# PART2.net
KiCad netlist of a schematic drawn in Altium Designer
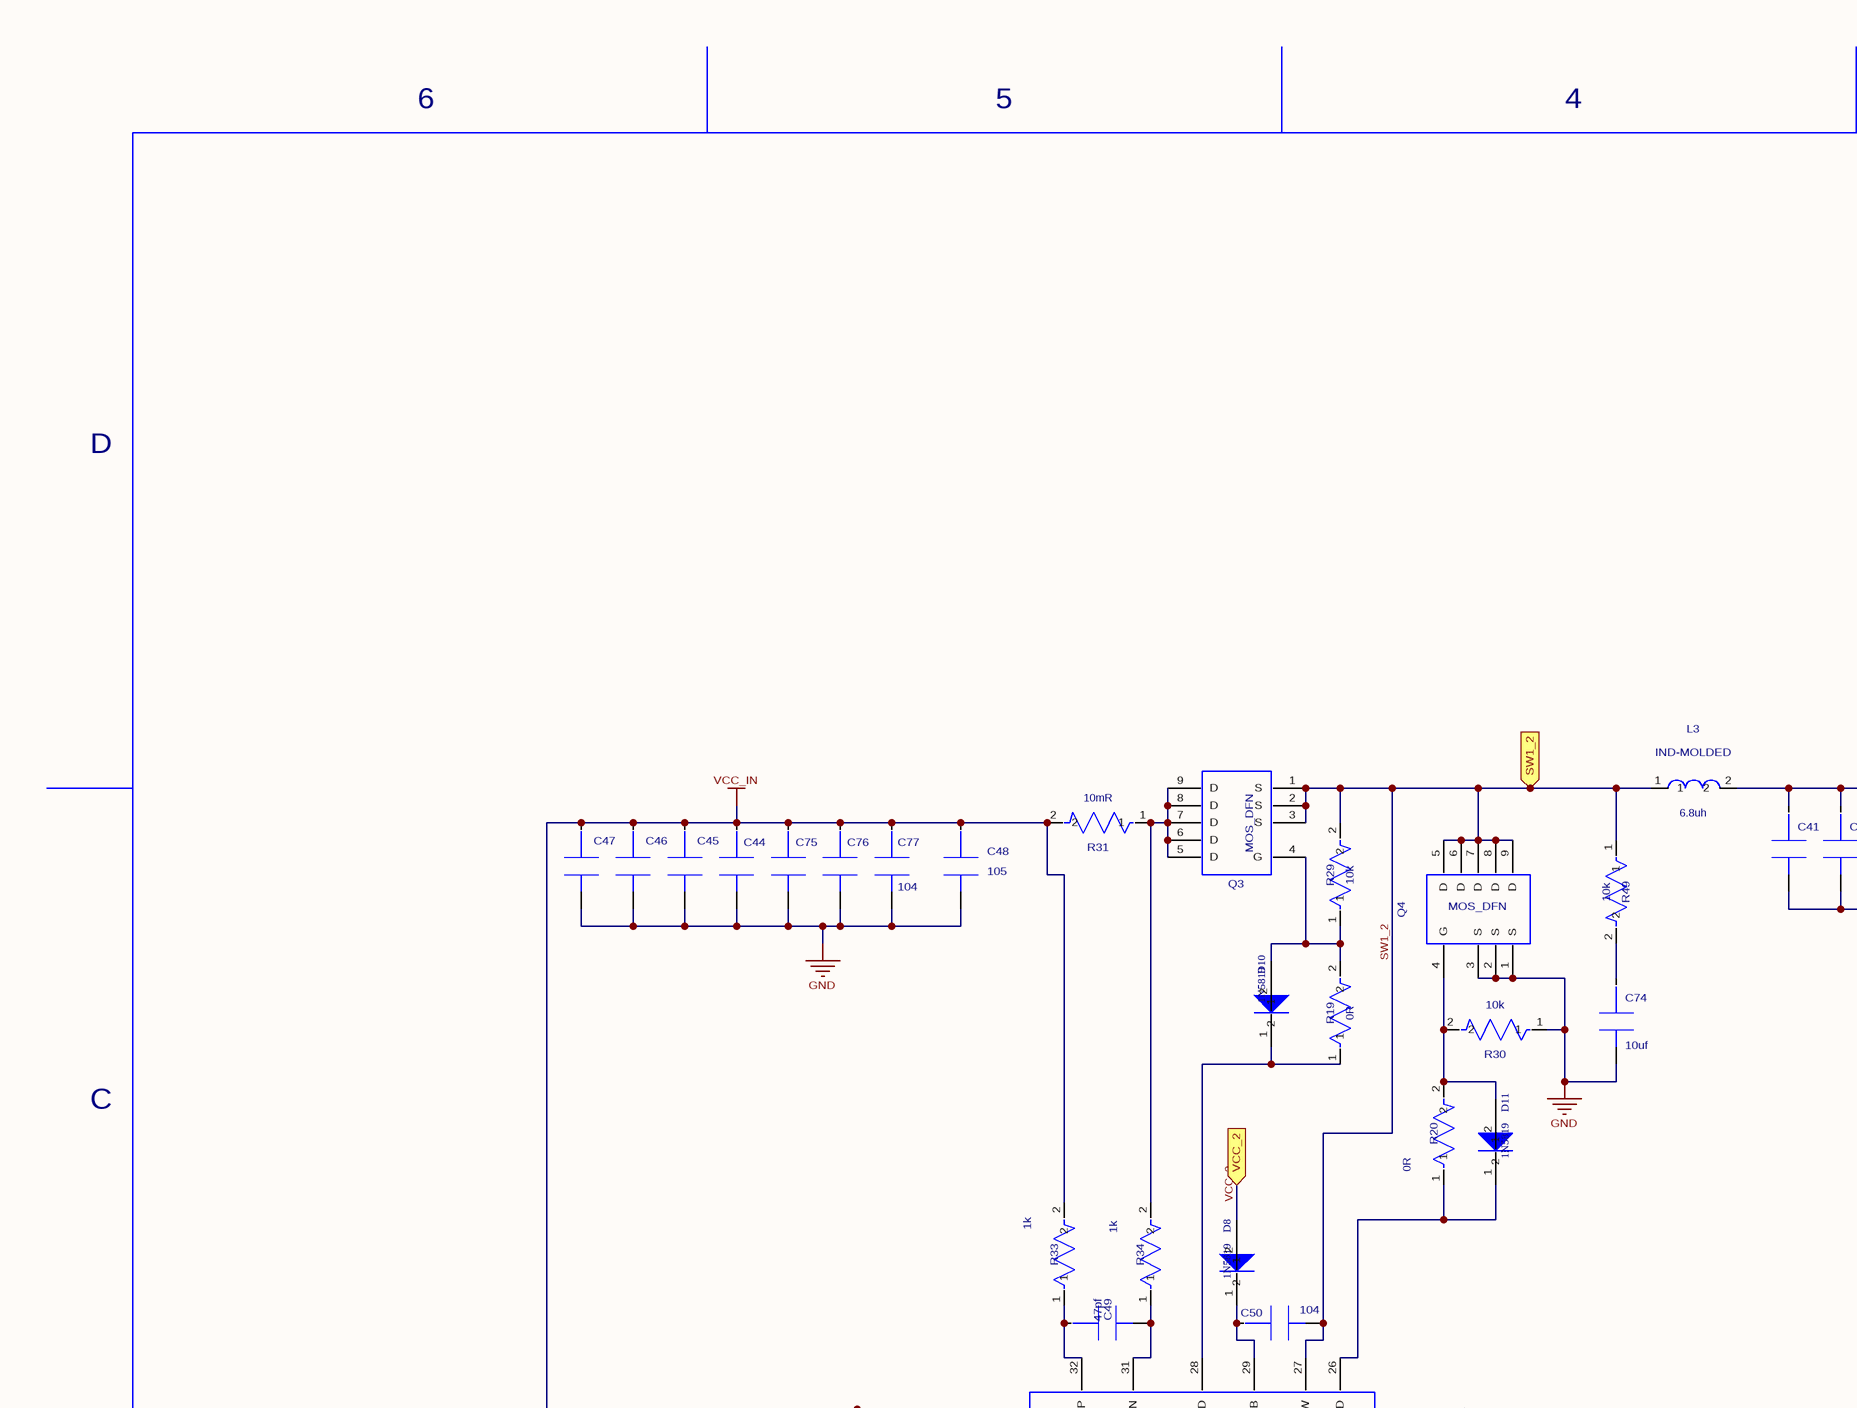
[diagram p0: PART2.SchDoc, top left]
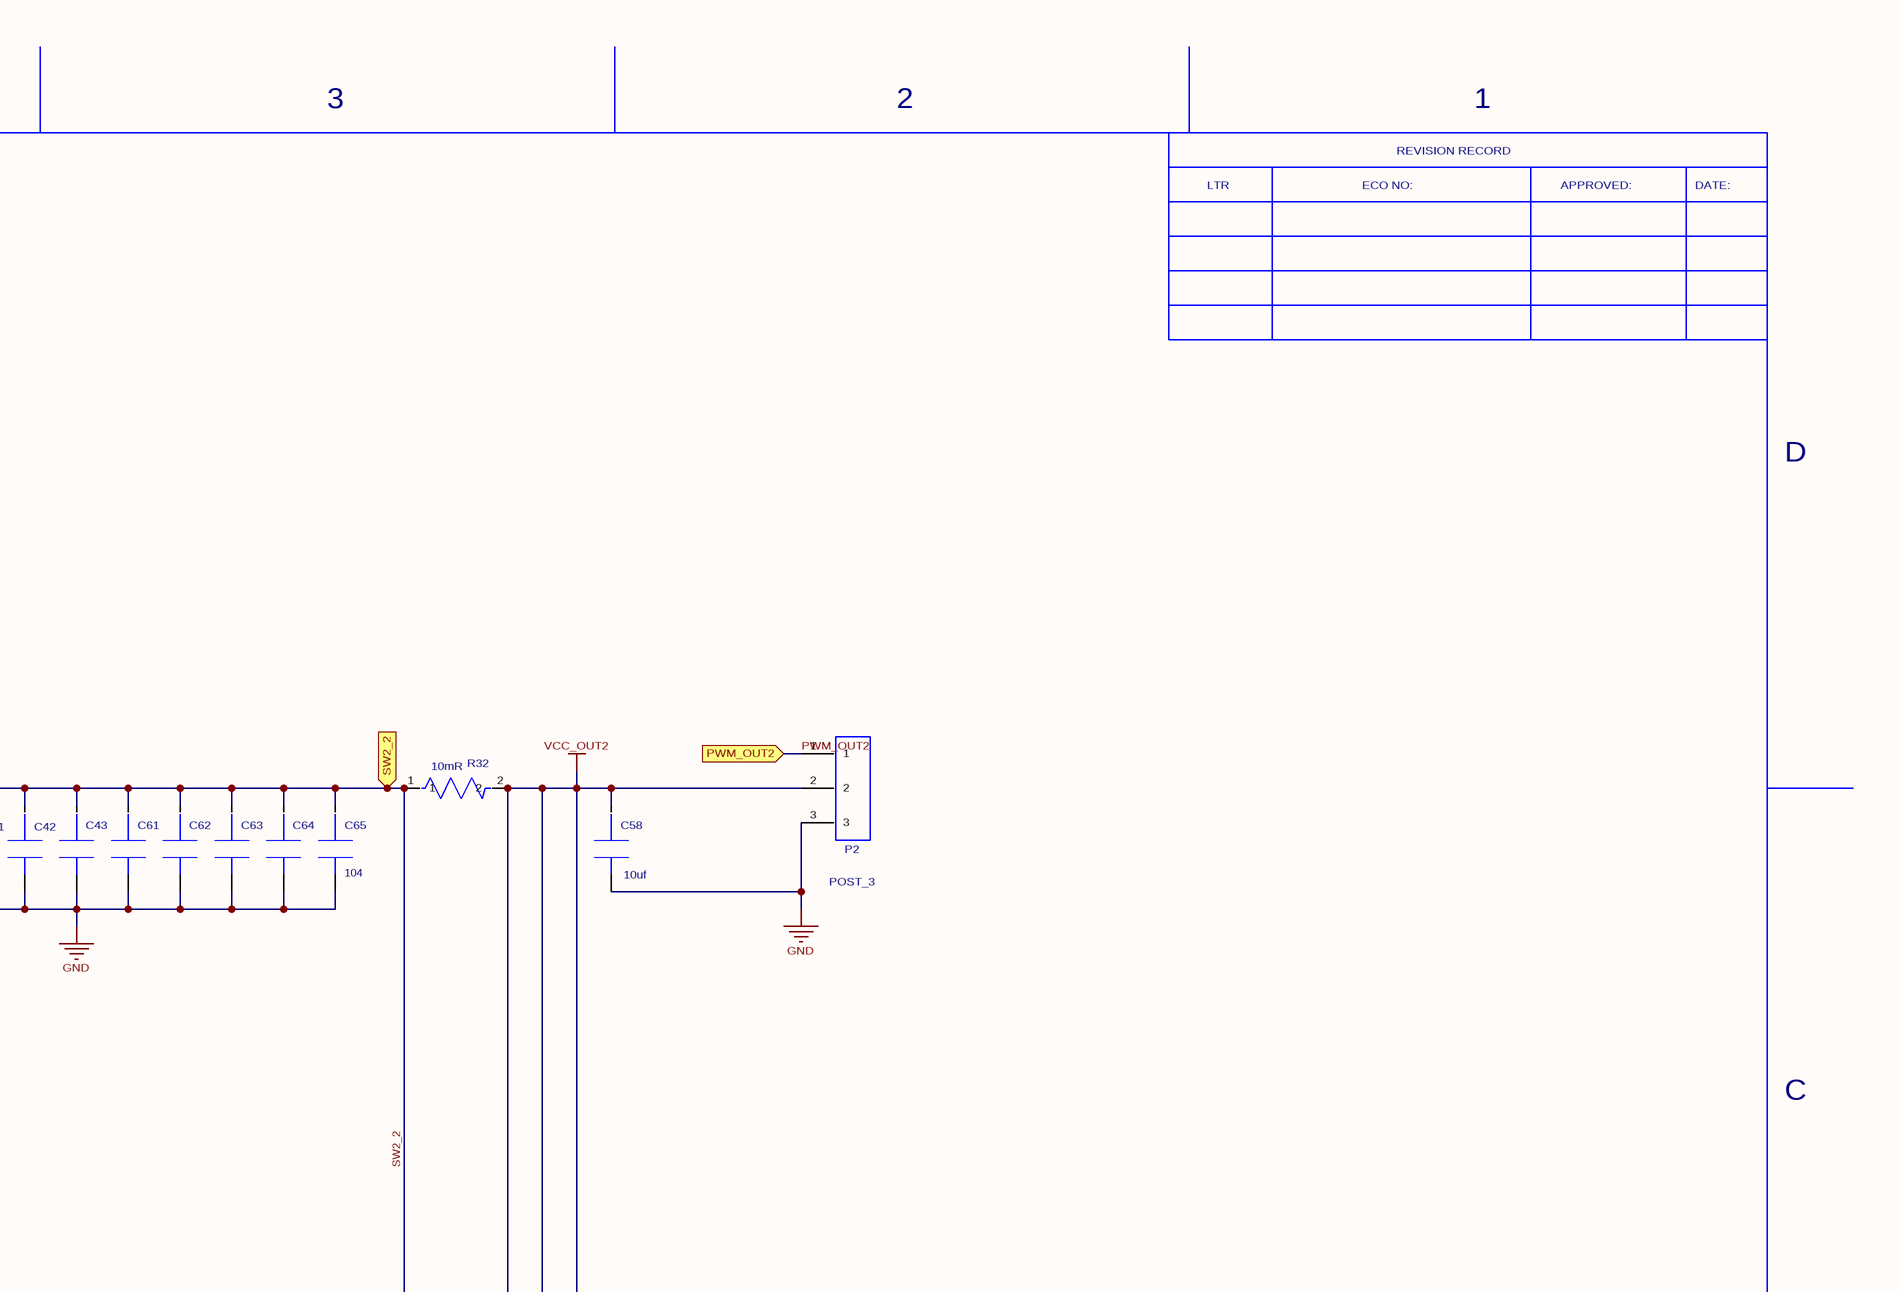
[diagram p1: PART2.SchDoc, top right]
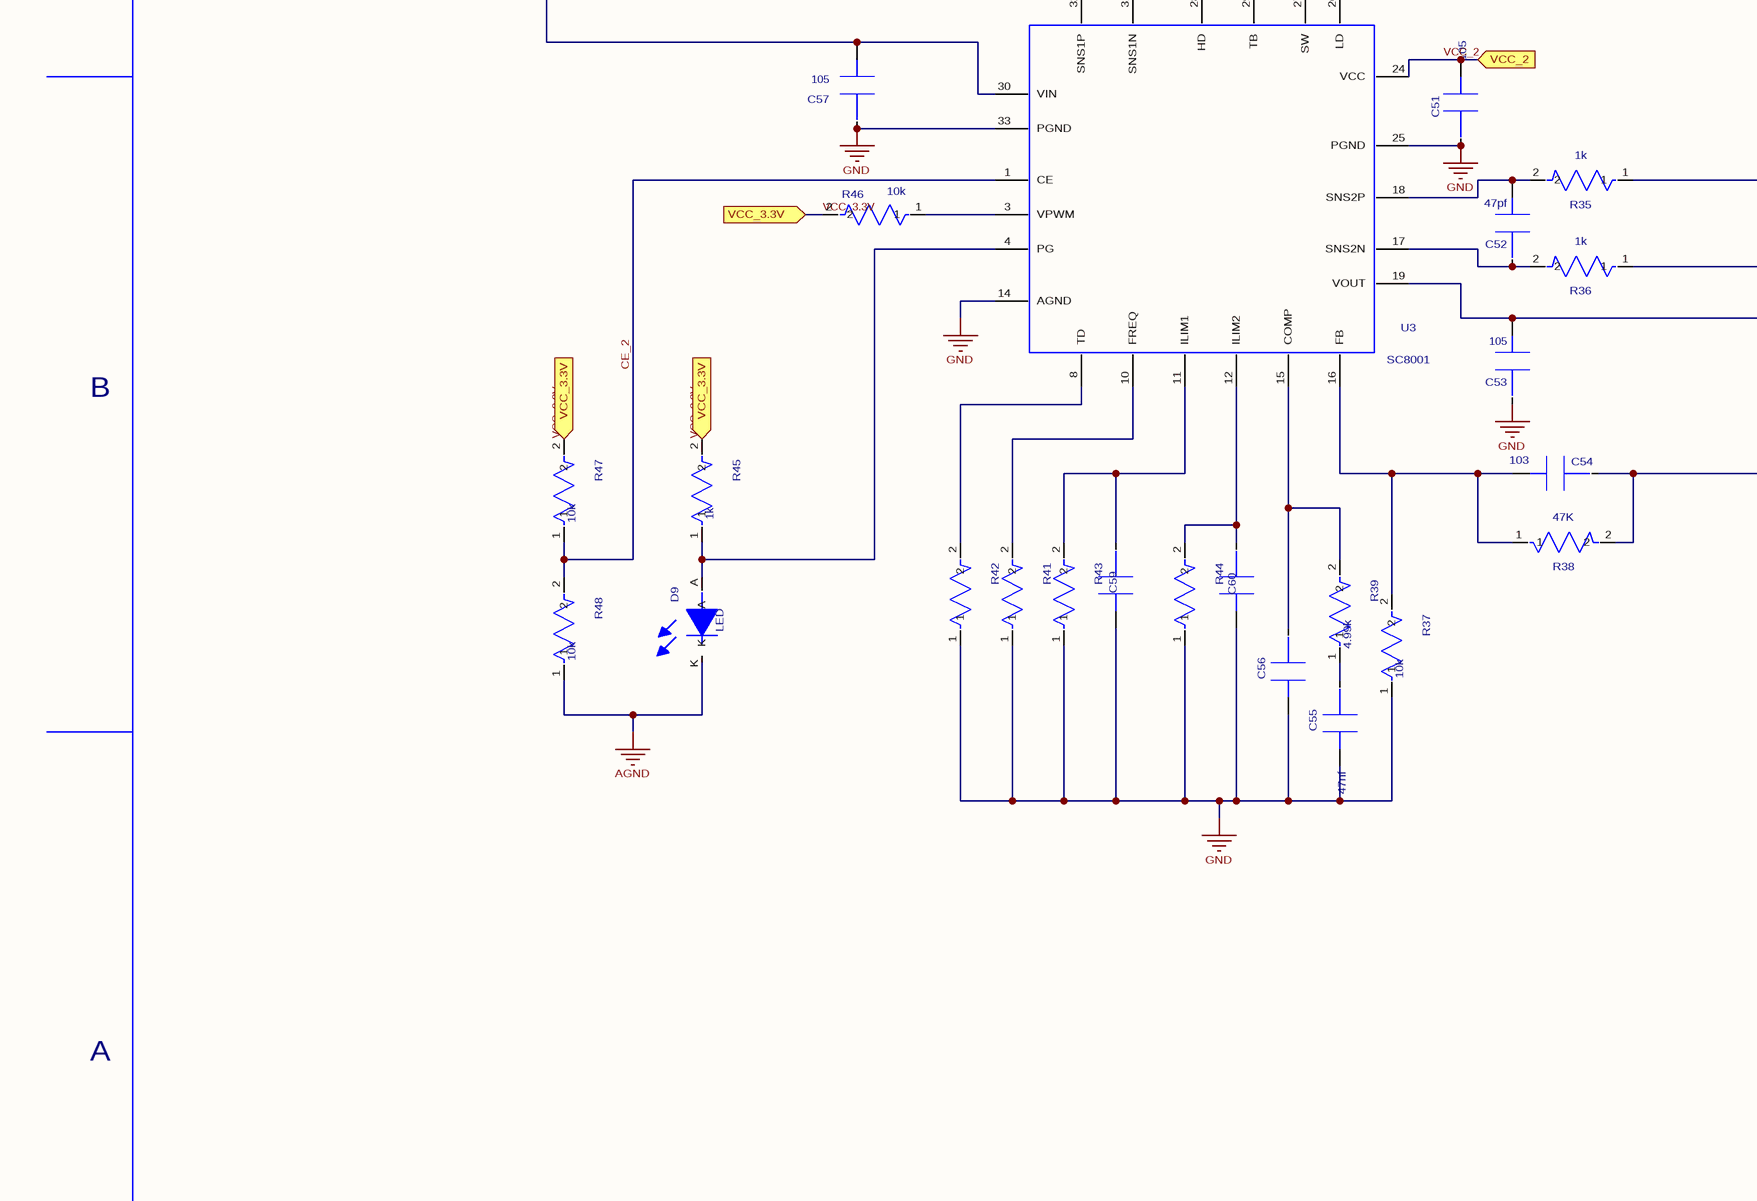
[diagram p2: PART2.SchDoc, bottom left]
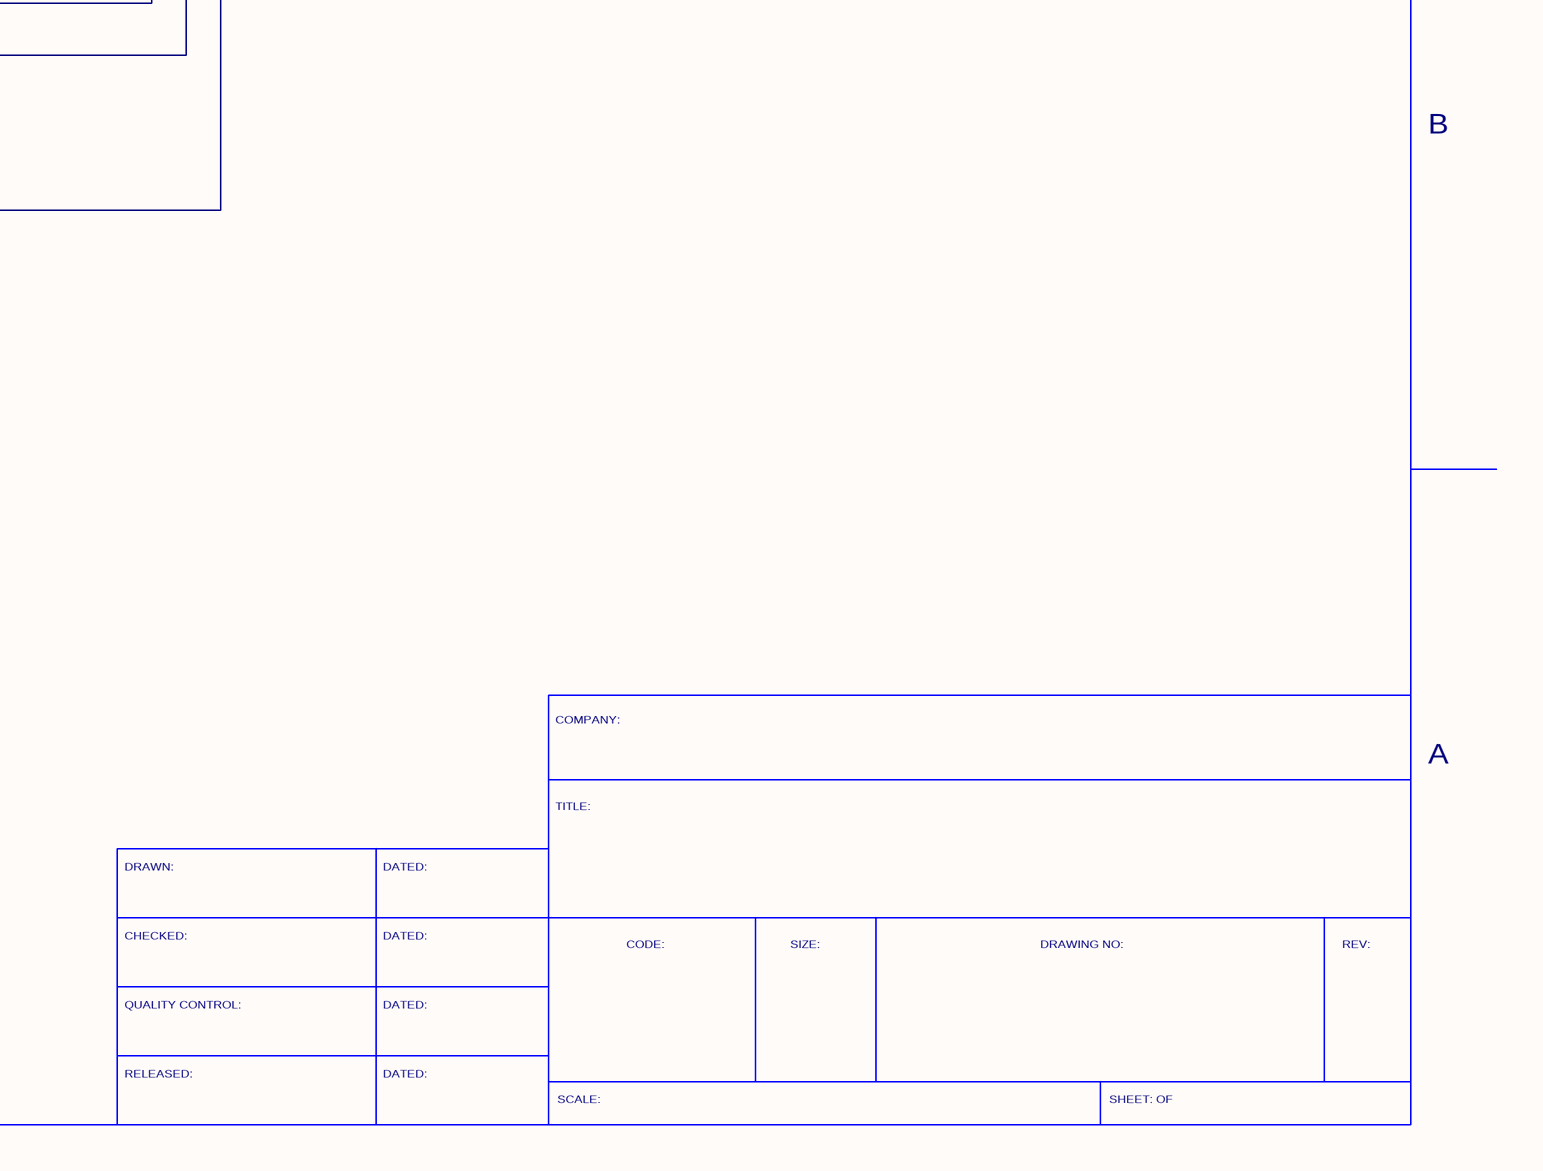
[diagram p3: PART2.SchDoc, bottom right]

(export (version "E")
  (design (tool "Eeschema 10.0.6"))
  (components
    (comp (ref "C41")
      (value "CAP-AE6.3")
      (footprint "CC6.56.5")
      (description "ALUMINUM ELECTROLYTIC CAP.")
      (libsource (lib "*") (part "CAP-AE6.3"))
    )
    (comp (ref "C42")
      (value "CAP-AE6.3")
      (footprint "CC6.56.5")
      (description "ALUMINUM ELECTROLYTIC CAP.")
      (libsource (lib "*") (part "CAP-AE6.3"))
    )
    (comp (ref "C43")
      (value "CAP-CFR04R-C")
      (footprint "1206C")
      (description "RADIAL FILM CAPACITOR, MIL-SPEC SIZE CFR04R SIZE 'C'")
      (fields (field (name "TOLERANCE") "???") (field (name "PART NUMBER") "TBD"))
      (libsource (lib "*") (part "CAP-CFR04R-C"))
    )
    (comp (ref "C44")
      (value "CAP-CFR04R-C")
      (footprint "1210C")
      (description "RADIAL FILM CAPACITOR, MIL-SPEC SIZE CFR04R SIZE 'C'")
      (fields (field (name "TOLERANCE") "???") (field (name "PART NUMBER") "TBD"))
      (libsource (lib "*") (part "CAP-CFR04R-C"))
    )
    (comp (ref "C45")
      (value "CAP-CFR04R-C")
      (footprint "1210C")
      (description "RADIAL FILM CAPACITOR, MIL-SPEC SIZE CFR04R SIZE 'C'")
      (fields (field (name "TOLERANCE") "???") (field (name "PART NUMBER") "TBD"))
      (libsource (lib "*") (part "CAP-CFR04R-C"))
    )
    (comp (ref "C46")
      (value "CAP-CFR04R-C")
      (footprint "1206C")
      (description "RADIAL FILM CAPACITOR, MIL-SPEC SIZE CFR04R SIZE 'C'")
      (fields (field (name "TOLERANCE") "???") (field (name "PART NUMBER") "TBD"))
      (libsource (lib "*") (part "CAP-CFR04R-C"))
    )
    (comp (ref "C47")
      (value "CAP-CFR04R-C")
      (footprint "1210C")
      (description "RADIAL FILM CAPACITOR, MIL-SPEC SIZE CFR04R SIZE 'C'")
      (fields (field (name "TOLERANCE") "???") (field (name "PART NUMBER") "TBD"))
      (libsource (lib "*") (part "CAP-CFR04R-C"))
    )
    (comp (ref "C48")
      (value "105")
      (footprint "0805C")
      (description "RADIAL FILM CAPACITOR, MIL-SPEC SIZE CFR04R SIZE 'C'")
      (fields (field (name "TOLERANCE") "???") (field (name "PART NUMBER") "TBD"))
      (libsource (lib "*") (part "CAP-CFR04R-C"))
    )
    (comp (ref "C49")
      (value "47pf")
      (footprint "0603C")
      (description "RADIAL FILM CAPACITOR, MIL-SPEC SIZE CFR04R SIZE 'C'")
      (fields (field (name "TOLERANCE") "???") (field (name "PART NUMBER") "TBD"))
      (libsource (lib "*") (part "CAP-CFR04R-C"))
    )
    (comp (ref "C50")
      (value "104")
      (footprint "0805C")
      (description "RADIAL FILM CAPACITOR, MIL-SPEC SIZE CFR04R SIZE 'C'")
      (fields (field (name "TOLERANCE") "???") (field (name "PART NUMBER") "TBD"))
      (libsource (lib "*") (part "CAP-CFR04R-C"))
    )
    (comp (ref "C51")
      (value "105")
      (footprint "0805C")
      (description "RADIAL FILM CAPACITOR, MIL-SPEC SIZE CFR04R SIZE 'C'")
      (fields (field (name "TOLERANCE") "???") (field (name "PART NUMBER") "TBD"))
      (libsource (lib "*") (part "CAP-CFR04R-C"))
    )
    (comp (ref "C52")
      (value "47pf")
      (footprint "0603C")
      (description "RADIAL FILM CAPACITOR, MIL-SPEC SIZE CFR04R SIZE 'C'")
      (fields (field (name "TOLERANCE") "???") (field (name "PART NUMBER") "TBD"))
      (libsource (lib "*") (part "CAP-CFR04R-C"))
    )
    (comp (ref "C53")
      (value "105")
      (footprint "0805C")
      (description "RADIAL FILM CAPACITOR, MIL-SPEC SIZE CFR04R SIZE 'C'")
      (fields (field (name "TOLERANCE") "???") (field (name "PART NUMBER") "TBD"))
      (libsource (lib "*") (part "CAP-CFR04R-C"))
    )
    (comp (ref "C54")
      (value "103")
      (footprint "0603C")
      (description "RADIAL FILM CAPACITOR, MIL-SPEC SIZE CFR04R SIZE 'C'")
      (fields (field (name "TOLERANCE") "???") (field (name "PART NUMBER") "TBD"))
      (libsource (lib "*") (part "CAP-CFR04R-C"))
    )
    (comp (ref "C55")
      (value "47nf")
      (footprint "0603C")
      (description "RADIAL FILM CAPACITOR, MIL-SPEC SIZE CFR04R SIZE 'C'")
      (fields (field (name "TOLERANCE") "???") (field (name "PART NUMBER") "TBD"))
      (libsource (lib "*") (part "CAP-CFR04R-C"))
    )
    (comp (ref "C56")
      (value "CAP-CFR04R-C")
      (footprint "0603C")
      (description "RADIAL FILM CAPACITOR, MIL-SPEC SIZE CFR04R SIZE 'C'")
      (fields (field (name "TOLERANCE") "???") (field (name "PART NUMBER") "TBD"))
      (libsource (lib "*") (part "CAP-CFR04R-C"))
    )
    (comp (ref "C57")
      (value "105")
      (footprint "0805C")
      (description "RADIAL FILM CAPACITOR, MIL-SPEC SIZE CFR04R SIZE 'C'")
      (fields (field (name "TOLERANCE") "???") (field (name "PART NUMBER") "TBD"))
      (libsource (lib "*") (part "CAP-CFR04R-C"))
    )
    (comp (ref "C58")
      (value "10uf")
      (footprint "1206C")
      (description "RADIAL FILM CAPACITOR, MIL-SPEC SIZE CFR04R SIZE 'C'")
      (fields (field (name "TOLERANCE") "???") (field (name "PART NUMBER") "TBD"))
      (libsource (lib "*") (part "CAP-CFR04R-C"))
    )
    (comp (ref "C59")
      (value "CAP-CFR04R-C")
      (footprint "0603C")
      (description "RADIAL FILM CAPACITOR, MIL-SPEC SIZE CFR04R SIZE 'C'")
      (fields (field (name "TOLERANCE") "???") (field (name "PART NUMBER") "TBD"))
      (libsource (lib "*") (part "CAP-CFR04R-C"))
    )
    (comp (ref "C60")
      (value "CAP-CFR04R-C")
      (footprint "0603C")
      (description "RADIAL FILM CAPACITOR, MIL-SPEC SIZE CFR04R SIZE 'C'")
      (fields (field (name "TOLERANCE") "???") (field (name "PART NUMBER") "TBD"))
      (libsource (lib "*") (part "CAP-CFR04R-C"))
    )
    (comp (ref "C61")
      (value "CAP-CFR04R-C")
      (footprint "1206C")
      (description "RADIAL FILM CAPACITOR, MIL-SPEC SIZE CFR04R SIZE 'C'")
      (fields (field (name "TOLERANCE") "???") (field (name "PART NUMBER") "TBD"))
      (libsource (lib "*") (part "CAP-CFR04R-C"))
    )
    (comp (ref "C62")
      (value "CAP-CFR04R-C")
      (footprint "1206C")
      (description "RADIAL FILM CAPACITOR, MIL-SPEC SIZE CFR04R SIZE 'C'")
      (fields (field (name "TOLERANCE") "???") (field (name "PART NUMBER") "TBD"))
      (libsource (lib "*") (part "CAP-CFR04R-C"))
    )
    (comp (ref "C63")
      (value "CAP-CFR04R-C")
      (footprint "1206C")
      (description "RADIAL FILM CAPACITOR, MIL-SPEC SIZE CFR04R SIZE 'C'")
      (fields (field (name "TOLERANCE") "???") (field (name "PART NUMBER") "TBD"))
      (libsource (lib "*") (part "CAP-CFR04R-C"))
    )
    (comp (ref "C64")
      (value "CAP-CFR04R-C")
      (footprint "1206C")
      (description "RADIAL FILM CAPACITOR, MIL-SPEC SIZE CFR04R SIZE 'C'")
      (fields (field (name "TOLERANCE") "???") (field (name "PART NUMBER") "TBD"))
      (libsource (lib "*") (part "CAP-CFR04R-C"))
    )
    (comp (ref "C65")
      (value "104")
      (footprint "1206C")
      (description "RADIAL FILM CAPACITOR, MIL-SPEC SIZE CFR04R SIZE 'C'")
      (fields (field (name "TOLERANCE") "???") (field (name "PART NUMBER") "TBD"))
      (libsource (lib "*") (part "CAP-CFR04R-C"))
    )
    (comp (ref "C74")
      (value "10uf")
      (footprint "0805C")
      (description "RADIAL FILM CAPACITOR, MIL-SPEC SIZE CFR04R SIZE 'C'")
      (fields (field (name "TOLERANCE") "???") (field (name "PART NUMBER") "TBD"))
      (libsource (lib "*") (part "CAP-CFR04R-C"))
    )
    (comp (ref "C75")
      (value "CAP-CFR04R-C")
      (footprint "1210C")
      (description "RADIAL FILM CAPACITOR, MIL-SPEC SIZE CFR04R SIZE 'C'")
      (fields (field (name "TOLERANCE") "???") (field (name "PART NUMBER") "TBD"))
      (libsource (lib "*") (part "CAP-CFR04R-C"))
    )
    (comp (ref "C76")
      (value "CAP-CFR04R-C")
      (footprint "1210C")
      (description "RADIAL FILM CAPACITOR, MIL-SPEC SIZE CFR04R SIZE 'C'")
      (fields (field (name "TOLERANCE") "???") (field (name "PART NUMBER") "TBD"))
      (libsource (lib "*") (part "CAP-CFR04R-C"))
    )
    (comp (ref "C77")
      (value "104")
      (footprint "0805C")
      (description "RADIAL FILM CAPACITOR, MIL-SPEC SIZE CFR04R SIZE 'C'")
      (fields (field (name "TOLERANCE") "???") (field (name "PART NUMBER") "TBD"))
      (libsource (lib "*") (part "CAP-CFR04R-C"))
    )
    (comp (ref "D8")
      (value "DIODE_1N4148")
      (footprint "SOD-123_L2.8-W1.8-LS3.7-RD")
      (description "High Conductance Fast Diode")
      (fields (field (name "PUBLISHER") "Altium Limited"))
      (libsource (lib "*") (part "DIODE_1N4148"))
    )
    (comp (ref "D9")
      (value "LED")
      (footprint "0805D")
      (description "LIGHT EMITTING DIODE")
      (libsource (lib "*") (part "LED"))
    )
    (comp (ref "D10")
      (value "DIODE_1N4148")
      (footprint "SOD-123_L2.8-W1.8-LS3.7-RD")
      (description "High Conductance Fast Diode")
      (fields (field (name "PUBLISHER") "Altium Limited"))
      (libsource (lib "*") (part "DIODE_1N4148"))
    )
    (comp (ref "D11")
      (value "DIODE_1N4148")
      (footprint "SOD-123_L2.8-W1.8-LS3.7-RD")
      (description "High Conductance Fast Diode")
      (fields (field (name "PUBLISHER") "Altium Limited"))
      (libsource (lib "*") (part "DIODE_1N4148"))
    )
    (comp (ref "L3")
      (value "IND-MOLDED")
      (footprint "1040L")
      (description "MOLDED INDUCTOR, 0.5\" PIN SPACING")
      (fields (field (name "ALTIUM_VALUE") "6.8uh"))
      (libsource (lib "*") (part "IND-MOLDED"))
    )
    (comp (ref "P2") (value "POST_3") (footprint "POST_3") (libsource (lib "*") (part "POST_3")))
    (comp (ref "Q3") (value "MOS_DFN") (footprint "DFN-8_5X6") (libsource (lib "*") (part "MOS_DFN")))
    (comp (ref "Q4") (value "MOS_DFN") (footprint "DFN-8_5X6") (libsource (lib "*") (part "MOS_DFN")))
    (comp (ref "R19")
      (value "0R")
      (footprint "0603R")
      (description "WIRE WOUND RESISTOR 3.4 X 7.05 MM")
      (fields (field (name "Comment") "RES-WR1"))
      (libsource (lib "*") (part "RES-WR1"))
    )
    (comp (ref "R20")
      (value "0R")
      (footprint "0603R")
      (description "WIRE WOUND RESISTOR 3.4 X 7.05 MM")
      (fields (field (name "Comment") "RES-WR1"))
      (libsource (lib "*") (part "RES-WR1"))
    )
    (comp (ref "R29")
      (value "10k")
      (footprint "0603R")
      (description "WIRE WOUND RESISTOR 3.4 X 7.05 MM")
      (fields (field (name "Comment") "RES-WR1"))
      (libsource (lib "*") (part "RES-WR1"))
    )
    (comp (ref "R30")
      (value "10k")
      (footprint "0603R")
      (description "WIRE WOUND RESISTOR 3.4 X 7.05 MM")
      (fields (field (name "Comment") "RES-WR1"))
      (libsource (lib "*") (part "RES-WR1"))
    )
    (comp (ref "R31")
      (value "10mR")
      (footprint "1206C")
      (description "WIRE WOUND RESISTOR 3.4 X 7.05 MM")
      (fields (field (name "Comment") "RES-WR1"))
      (libsource (lib "*") (part "RES-WR1"))
    )
    (comp (ref "R32")
      (value "10mR")
      (footprint "1206C")
      (description "WIRE WOUND RESISTOR 3.4 X 7.05 MM")
      (fields (field (name "Comment") "RES-WR1"))
      (libsource (lib "*") (part "RES-WR1"))
    )
    (comp (ref "R33")
      (value "1k")
      (footprint "0603R")
      (description "WIRE WOUND RESISTOR 3.4 X 7.05 MM")
      (fields (field (name "Comment") "RES-WR1"))
      (libsource (lib "*") (part "RES-WR1"))
    )
    (comp (ref "R34")
      (value "1k")
      (footprint "0603R")
      (description "WIRE WOUND RESISTOR 3.4 X 7.05 MM")
      (fields (field (name "Comment") "RES-WR1"))
      (libsource (lib "*") (part "RES-WR1"))
    )
    (comp (ref "R35")
      (value "1k")
      (footprint "0603R")
      (description "WIRE WOUND RESISTOR 3.4 X 7.05 MM")
      (fields (field (name "Comment") "RES-WR1"))
      (libsource (lib "*") (part "RES-WR1"))
    )
    (comp (ref "R36")
      (value "1k")
      (footprint "0603R")
      (description "WIRE WOUND RESISTOR 3.4 X 7.05 MM")
      (fields (field (name "Comment") "RES-WR1"))
      (libsource (lib "*") (part "RES-WR1"))
    )
    (comp (ref "R37")
      (value "10k")
      (footprint "0603R")
      (description "WIRE WOUND RESISTOR 3.4 X 7.05 MM")
      (fields (field (name "Comment") "RES-WR1"))
      (libsource (lib "*") (part "RES-WR1"))
    )
    (comp (ref "R38")
      (value "47K")
      (footprint "0603R")
      (description "WIRE WOUND RESISTOR 3.4 X 7.05 MM")
      (fields (field (name "Comment") "RES-WR1"))
      (libsource (lib "*") (part "RES-WR1"))
    )
    (comp (ref "R39")
      (value "4.99k")
      (footprint "0603R")
      (description "WIRE WOUND RESISTOR 3.4 X 7.05 MM")
      (fields (field (name "Comment") "RES-WR1"))
      (libsource (lib "*") (part "RES-WR1"))
    )
    (comp (ref "R41")
      (value "RES-WR1")
      (footprint "0603R")
      (description "WIRE WOUND RESISTOR 3.4 X 7.05 MM")
      (libsource (lib "*") (part "RES-WR1"))
    )
    (comp (ref "R42")
      (value "RES-WR1")
      (footprint "0603R")
      (description "WIRE WOUND RESISTOR 3.4 X 7.05 MM")
      (libsource (lib "*") (part "RES-WR1"))
    )
    (comp (ref "R43")
      (value "RES-WR1")
      (footprint "0603R")
      (description "WIRE WOUND RESISTOR 3.4 X 7.05 MM")
      (libsource (lib "*") (part "RES-WR1"))
    )
    (comp (ref "R44")
      (value "RES-WR1")
      (footprint "0603R")
      (description "WIRE WOUND RESISTOR 3.4 X 7.05 MM")
      (libsource (lib "*") (part "RES-WR1"))
    )
    (comp (ref "R45")
      (value "1k")
      (footprint "0805R")
      (description "WIRE WOUND RESISTOR 3.4 X 7.05 MM")
      (fields (field (name "Comment") "RES-WR1"))
      (libsource (lib "*") (part "RES-WR1"))
    )
    (comp (ref "R46")
      (value "10k")
      (footprint "0805R")
      (description "WIRE WOUND RESISTOR 3.4 X 7.05 MM")
      (fields (field (name "Comment") "RES-WR1"))
      (libsource (lib "*") (part "RES-WR1"))
    )
    (comp (ref "R47")
      (value "10k")
      (footprint "0805R")
      (description "WIRE WOUND RESISTOR 3.4 X 7.05 MM")
      (fields (field (name "Comment") "RES-WR1"))
      (libsource (lib "*") (part "RES-WR1"))
    )
    (comp (ref "R48")
      (value "10k")
      (footprint "0805R")
      (description "WIRE WOUND RESISTOR 3.4 X 7.05 MM")
      (fields (field (name "Comment") "RES-WR1"))
      (libsource (lib "*") (part "RES-WR1"))
    )
    (comp (ref "R49")
      (value "10k")
      (footprint "1206C")
      (description "WIRE WOUND RESISTOR 3.4 X 7.05 MM")
      (fields (field (name "Comment") "RES-WR1"))
      (libsource (lib "*") (part "RES-WR1"))
    )
    (comp (ref "U3")
      (value "SC8001")
      (footprint "QFN-32_L4.0-W4.0-P0.40-BL-EP2.7")
      (libsource (lib "*") (part "SC8001"))
    )
  )
  (nets
    (net (code "1") (name "/CE_2") (class "Default")
      (node (ref "R47") (pin "1") (pinfunction "1_1") (pintype "passive"))
      (node (ref "R48") (pin "2") (pinfunction "2_2") (pintype "passive"))
      (node (ref "U3") (pin "1") (pinfunction "CE_1") (pintype "passive"))
    )
    (net (code "2") (name "/PWM_OUT2") (class "Default")
      (node (ref "P2") (pin "1") (pinfunction "1_1") (pintype "passive"))
    )
    (net (code "3") (name "/SW1_2") (class "Default")
      (node (ref "C50") (pin "2") (pinfunction "2_2") (pintype "passive"))
      (node (ref "L3") (pin "1") (pinfunction "1_1") (pintype "passive"))
      (node (ref "Q3") (pin "1") (pinfunction "S_1") (pintype "passive"))
      (node (ref "Q3") (pin "2") (pinfunction "S_2") (pintype "passive"))
      (node (ref "Q3") (pin "3") (pinfunction "S_3") (pintype "passive"))
      (node (ref "Q4") (pin "5") (pinfunction "D_5") (pintype "passive"))
      (node (ref "Q4") (pin "6") (pinfunction "D_6") (pintype "passive"))
      (node (ref "Q4") (pin "7") (pinfunction "D_7") (pintype "passive"))
      (node (ref "Q4") (pin "8") (pinfunction "D_8") (pintype "passive"))
      (node (ref "Q4") (pin "9") (pinfunction "D_9") (pintype "passive"))
      (node (ref "R29") (pin "2") (pinfunction "2_2") (pintype "passive"))
      (node (ref "R49") (pin "1") (pinfunction "1_1") (pintype "passive"))
      (node (ref "U3") (pin "27") (pinfunction "SW_27") (pintype "passive"))
    )
    (net (code "4") (name "/SW2_2") (class "Default")
      (node (ref "C41") (pin "1") (pinfunction "1_1") (pintype "passive"))
      (node (ref "C42") (pin "1") (pinfunction "1_1") (pintype "passive"))
      (node (ref "C43") (pin "1") (pinfunction "1_1") (pintype "passive"))
      (node (ref "C61") (pin "1") (pinfunction "1_1") (pintype "passive"))
      (node (ref "C62") (pin "1") (pinfunction "1_1") (pintype "passive"))
      (node (ref "C63") (pin "1") (pinfunction "1_1") (pintype "passive"))
      (node (ref "C64") (pin "1") (pinfunction "1_1") (pintype "passive"))
      (node (ref "C65") (pin "1") (pinfunction "1_1") (pintype "passive"))
      (node (ref "L3") (pin "2") (pinfunction "2_2") (pintype "passive"))
      (node (ref "R32") (pin "1") (pinfunction "1_1") (pintype "passive"))
      (node (ref "R35") (pin "1") (pinfunction "1_1") (pintype "passive"))
    )
    (net (code "5") (name "/VCC_2") (class "Default")
      (node (ref "C51") (pin "2") (pinfunction "2_2") (pintype "passive"))
      (node (ref "D8") (pin "2") (pinfunction "2_2") (pintype "passive"))
      (node (ref "U3") (pin "24") (pinfunction "VCC_24") (pintype "passive"))
    )
    (net (code "6") (name "/VCC_3.3V") (class "Default")
      (node (ref "R45") (pin "2") (pinfunction "2_2") (pintype "passive"))
      (node (ref "R46") (pin "2") (pinfunction "2_2") (pintype "passive"))
      (node (ref "R47") (pin "2") (pinfunction "2_2") (pintype "passive"))
    )
    (net (code "7") (name "AGND") (class "Default")
      (node (ref "D9") (pin "K") (pinfunction "K_K") (pintype "passive"))
      (node (ref "R48") (pin "1") (pinfunction "1_1") (pintype "passive"))
    )
    (net (code "8") (name "GND") (class "Default")
      (node (ref "C41") (pin "2") (pinfunction "2_2") (pintype "passive"))
      (node (ref "C42") (pin "2") (pinfunction "2_2") (pintype "passive"))
      (node (ref "C43") (pin "2") (pinfunction "2_2") (pintype "passive"))
      (node (ref "C44") (pin "2") (pinfunction "2_2") (pintype "passive"))
      (node (ref "C45") (pin "2") (pinfunction "2_2") (pintype "passive"))
      (node (ref "C46") (pin "2") (pinfunction "2_2") (pintype "passive"))
      (node (ref "C47") (pin "2") (pinfunction "2_2") (pintype "passive"))
      (node (ref "C48") (pin "2") (pinfunction "2_2") (pintype "passive"))
      (node (ref "C51") (pin "1") (pinfunction "1_1") (pintype "passive"))
      (node (ref "C53") (pin "1") (pinfunction "1_1") (pintype "passive"))
      (node (ref "C55") (pin "2") (pinfunction "2_2") (pintype "passive"))
      (node (ref "C56") (pin "2") (pinfunction "2_2") (pintype "passive"))
      (node (ref "C57") (pin "1") (pinfunction "1_1") (pintype "passive"))
      (node (ref "C58") (pin "2") (pinfunction "2_2") (pintype "passive"))
      (node (ref "C59") (pin "2") (pinfunction "2_2") (pintype "passive"))
      (node (ref "C60") (pin "2") (pinfunction "2_2") (pintype "passive"))
      (node (ref "C61") (pin "2") (pinfunction "2_2") (pintype "passive"))
      (node (ref "C62") (pin "2") (pinfunction "2_2") (pintype "passive"))
      (node (ref "C63") (pin "2") (pinfunction "2_2") (pintype "passive"))
      (node (ref "C64") (pin "2") (pinfunction "2_2") (pintype "passive"))
      (node (ref "C65") (pin "2") (pinfunction "2_2") (pintype "passive"))
      (node (ref "C74") (pin "2") (pinfunction "2_2") (pintype "passive"))
      (node (ref "C75") (pin "2") (pinfunction "2_2") (pintype "passive"))
      (node (ref "C76") (pin "2") (pinfunction "2_2") (pintype "passive"))
      (node (ref "C77") (pin "2") (pinfunction "2_2") (pintype "passive"))
      (node (ref "P2") (pin "3") (pinfunction "3_3") (pintype "passive"))
      (node (ref "Q4") (pin "1") (pinfunction "S_1") (pintype "passive"))
      (node (ref "Q4") (pin "2") (pinfunction "S_2") (pintype "passive"))
      (node (ref "Q4") (pin "3") (pinfunction "S_3") (pintype "passive"))
      (node (ref "R30") (pin "1") (pinfunction "1_1") (pintype "passive"))
      (node (ref "R37") (pin "1") (pinfunction "1_1") (pintype "passive"))
      (node (ref "R41") (pin "1") (pinfunction "1_1") (pintype "passive"))
      (node (ref "R42") (pin "1") (pinfunction "1_1") (pintype "passive"))
      (node (ref "R43") (pin "1") (pinfunction "1_1") (pintype "passive"))
      (node (ref "R44") (pin "1") (pinfunction "1_1") (pintype "passive"))
      (node (ref "U3") (pin "14") (pinfunction "AGND_14") (pintype "passive"))
      (node (ref "U3") (pin "25") (pinfunction "PGND_25") (pintype "passive"))
      (node (ref "U3") (pin "33") (pinfunction "PGND_33") (pintype "passive"))
    )
    (net (code "9") (name "Net-(C55-Pad1)") (class "Default")
      (node (ref "C55") (pin "1") (pinfunction "1_1") (pintype "passive"))
      (node (ref "R39") (pin "1") (pinfunction "1_1") (pintype "passive"))
    )
    (net (code "10") (name "Net-(C74-Pad1)") (class "Default")
      (node (ref "C74") (pin "1") (pinfunction "1_1") (pintype "passive"))
      (node (ref "R49") (pin "2") (pinfunction "2_2") (pintype "passive"))
    )
    (net (code "11") (name "Net-(Q3-D-Pad5)") (class "Default")
      (node (ref "Q3") (pin "5") (pinfunction "D_5") (pintype "passive"))
      (node (ref "Q3") (pin "6") (pinfunction "D_6") (pintype "passive"))
      (node (ref "Q3") (pin "7") (pinfunction "D_7") (pintype "passive"))
      (node (ref "Q3") (pin "8") (pinfunction "D_8") (pintype "passive"))
      (node (ref "Q3") (pin "9") (pinfunction "D_9") (pintype "passive"))
      (node (ref "R31") (pin "1") (pinfunction "1_1") (pintype "passive"))
      (node (ref "R34") (pin "2") (pinfunction "2_2") (pintype "passive"))
    )
    (net (code "12") (name "Net-(Q3-G)") (class "Default")
      (node (ref "D10") (pin "2") (pinfunction "2_2") (pintype "passive"))
      (node (ref "Q3") (pin "4") (pinfunction "G_4") (pintype "passive"))
      (node (ref "R19") (pin "2") (pinfunction "2_2") (pintype "passive"))
      (node (ref "R29") (pin "1") (pinfunction "1_1") (pintype "passive"))
    )
    (net (code "13") (name "Net-(Q4-G)") (class "Default")
      (node (ref "D11") (pin "2") (pinfunction "2_2") (pintype "passive"))
      (node (ref "Q4") (pin "4") (pinfunction "G_4") (pintype "passive"))
      (node (ref "R20") (pin "2") (pinfunction "2_2") (pintype "passive"))
      (node (ref "R30") (pin "2") (pinfunction "2_2") (pintype "passive"))
    )
    (net (code "14") (name "Net-(U3-COMP)") (class "Default")
      (node (ref "C56") (pin "1") (pinfunction "1_1") (pintype "passive"))
      (node (ref "R39") (pin "2") (pinfunction "2_2") (pintype "passive"))
      (node (ref "U3") (pin "15") (pinfunction "COMP_15") (pintype "passive"))
    )
    (net (code "15") (name "Net-(U3-FB)") (class "Default")
      (node (ref "C54") (pin "2") (pinfunction "2_2") (pintype "passive"))
      (node (ref "R37") (pin "2") (pinfunction "2_2") (pintype "passive"))
      (node (ref "R38") (pin "1") (pinfunction "1_1") (pintype "passive"))
      (node (ref "U3") (pin "16") (pinfunction "FB_16") (pintype "passive"))
    )
    (net (code "16") (name "Net-(U3-FREQ)") (class "Default")
      (node (ref "R41") (pin "2") (pinfunction "2_2") (pintype "passive"))
      (node (ref "U3") (pin "10") (pinfunction "FREQ_10") (pintype "passive"))
    )
    (net (code "17") (name "Net-(U3-HD)") (class "Default")
      (node (ref "D10") (pin "1") (pinfunction "1_1") (pintype "passive"))
      (node (ref "R19") (pin "1") (pinfunction "1_1") (pintype "passive"))
      (node (ref "U3") (pin "28") (pinfunction "HD_28") (pintype "passive"))
    )
    (net (code "18") (name "Net-(U3-ILIM1)") (class "Default")
      (node (ref "C59") (pin "1") (pinfunction "1_1") (pintype "passive"))
      (node (ref "R43") (pin "2") (pinfunction "2_2") (pintype "passive"))
      (node (ref "U3") (pin "11") (pinfunction "ILIM1_11") (pintype "passive"))
    )
    (net (code "19") (name "Net-(U3-ILIM2)") (class "Default")
      (node (ref "C60") (pin "1") (pinfunction "1_1") (pintype "passive"))
      (node (ref "R44") (pin "2") (pinfunction "2_2") (pintype "passive"))
      (node (ref "U3") (pin "12") (pinfunction "ILIM2_12") (pintype "passive"))
    )
    (net (code "20") (name "Net-(U3-LD)") (class "Default")
      (node (ref "D11") (pin "1") (pinfunction "1_1") (pintype "passive"))
      (node (ref "R20") (pin "1") (pinfunction "1_1") (pintype "passive"))
      (node (ref "U3") (pin "26") (pinfunction "LD_26") (pintype "passive"))
    )
    (net (code "21") (name "Net-(U3-PG)") (class "Default")
      (node (ref "D9") (pin "A") (pinfunction "A_A") (pintype "passive"))
      (node (ref "R45") (pin "1") (pinfunction "1_1") (pintype "passive"))
      (node (ref "U3") (pin "4") (pinfunction "PG_4") (pintype "passive"))
    )
    (net (code "22") (name "Net-(U3-SNS1N)") (class "Default")
      (node (ref "C49") (pin "2") (pinfunction "2_2") (pintype "passive"))
      (node (ref "R34") (pin "1") (pinfunction "1_1") (pintype "passive"))
      (node (ref "U3") (pin "31") (pinfunction "SNS1N_31") (pintype "passive"))
    )
    (net (code "23") (name "Net-(U3-SNS1P)") (class "Default")
      (node (ref "C49") (pin "1") (pinfunction "1_1") (pintype "passive"))
      (node (ref "R33") (pin "1") (pinfunction "1_1") (pintype "passive"))
      (node (ref "U3") (pin "32") (pinfunction "SNS1P_32") (pintype "passive"))
    )
    (net (code "24") (name "Net-(U3-SNS2N)") (class "Default")
      (node (ref "C52") (pin "1") (pinfunction "1_1") (pintype "passive"))
      (node (ref "R36") (pin "2") (pinfunction "2_2") (pintype "passive"))
      (node (ref "U3") (pin "17") (pinfunction "SNS2N_17") (pintype "passive"))
    )
    (net (code "25") (name "Net-(U3-SNS2P)") (class "Default")
      (node (ref "C52") (pin "2") (pinfunction "2_2") (pintype "passive"))
      (node (ref "R35") (pin "2") (pinfunction "2_2") (pintype "passive"))
      (node (ref "U3") (pin "18") (pinfunction "SNS2P_18") (pintype "passive"))
    )
    (net (code "26") (name "Net-(U3-TB)") (class "Default")
      (node (ref "C50") (pin "1") (pinfunction "1_1") (pintype "passive"))
      (node (ref "D8") (pin "1") (pinfunction "1_1") (pintype "passive"))
      (node (ref "U3") (pin "29") (pinfunction "TB_29") (pintype "passive"))
    )
    (net (code "27") (name "Net-(U3-TD)") (class "Default")
      (node (ref "R42") (pin "2") (pinfunction "2_2") (pintype "passive"))
      (node (ref "U3") (pin "8") (pinfunction "TD_8") (pintype "passive"))
    )
    (net (code "28") (name "Net-(U3-VPWM)") (class "Default")
      (node (ref "R46") (pin "1") (pinfunction "1_1") (pintype "passive"))
      (node (ref "U3") (pin "3") (pinfunction "VPWM_3") (pintype "passive"))
    )
    (net (code "29") (name "VCC_IN") (class "Default")
      (node (ref "C44") (pin "1") (pinfunction "1_1") (pintype "passive"))
      (node (ref "C45") (pin "1") (pinfunction "1_1") (pintype "passive"))
      (node (ref "C46") (pin "1") (pinfunction "1_1") (pintype "passive"))
      (node (ref "C47") (pin "1") (pinfunction "1_1") (pintype "passive"))
      (node (ref "C48") (pin "1") (pinfunction "1_1") (pintype "passive"))
      (node (ref "C57") (pin "2") (pinfunction "2_2") (pintype "passive"))
      (node (ref "C75") (pin "1") (pinfunction "1_1") (pintype "passive"))
      (node (ref "C76") (pin "1") (pinfunction "1_1") (pintype "passive"))
      (node (ref "C77") (pin "1") (pinfunction "1_1") (pintype "passive"))
      (node (ref "R31") (pin "2") (pinfunction "2_2") (pintype "passive"))
      (node (ref "R33") (pin "2") (pinfunction "2_2") (pintype "passive"))
      (node (ref "U3") (pin "30") (pinfunction "VIN_30") (pintype "passive"))
    )
    (net (code "30") (name "VCC_OUT2") (class "Default")
      (node (ref "C53") (pin "2") (pinfunction "2_2") (pintype "passive"))
      (node (ref "C54") (pin "1") (pinfunction "1_1") (pintype "passive"))
      (node (ref "C58") (pin "1") (pinfunction "1_1") (pintype "passive"))
      (node (ref "P2") (pin "2") (pinfunction "2_2") (pintype "passive"))
      (node (ref "R32") (pin "2") (pinfunction "2_2") (pintype "passive"))
      (node (ref "R36") (pin "1") (pinfunction "1_1") (pintype "passive"))
      (node (ref "R38") (pin "2") (pinfunction "2_2") (pintype "passive"))
      (node (ref "U3") (pin "19") (pinfunction "VOUT_19") (pintype "passive"))
    )
  )
)
